# Control_System.net
KiCad netlist of a schematic drawn in Altium Designer
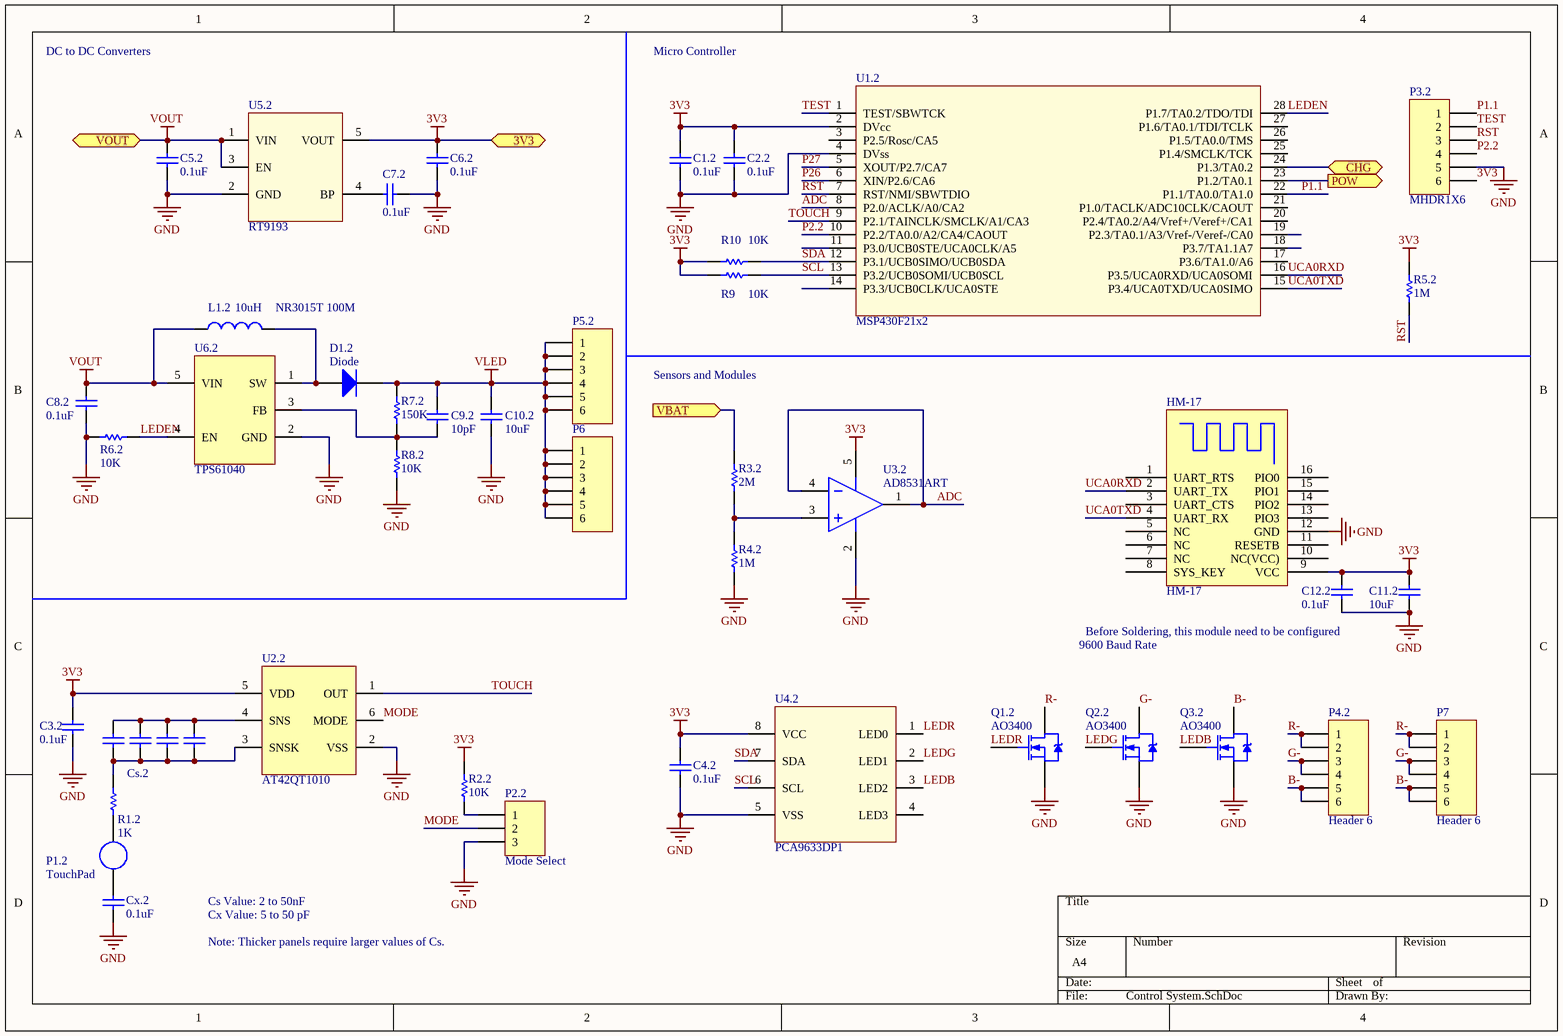
[diagram p0: Control System.SchDoc]

(export (version "E")
  (design (tool "Eeschema 10.0.6"))
  (components
    (comp (ref "C1.2")
      (value "0.1uF")
      (footprint "D0603")
      (description "Capacitor")
      (fields (field (name "Comment") "0603") (field (name "PUBLISHER") "Altium Limited"))
      (libsource (lib "Miscellaneous Devices") (part "Cap"))
    )
    (comp (ref "C2.2")
      (value "0.1uF")
      (footprint "D0603")
      (description "Capacitor")
      (fields (field (name "Comment") "0603") (field (name "PUBLISHER") "Altium Limited"))
      (libsource (lib "Miscellaneous Devices") (part "Cap"))
    )
    (comp (ref "C3.2")
      (value "0.1uF")
      (footprint "D0603")
      (description "Capacitor")
      (fields (field (name "Comment") "0603") (field (name "PUBLISHER") "Altium Limited"))
      (libsource (lib "Miscellaneous Devices") (part "Cap"))
    )
    (comp (ref "C4.2")
      (value "0.1uF")
      (footprint "D0603")
      (description "Capacitor")
      (fields (field (name "Comment") "0603") (field (name "PUBLISHER") "Altium Limited"))
      (libsource (lib "Miscellaneous Devices") (part "Cap"))
    )
    (comp (ref "C5.2")
      (value "0.1uF")
      (footprint "D0603")
      (description "Capacitor")
      (fields (field (name "Comment") "0603") (field (name "PUBLISHER") "Altium Limited"))
      (libsource (lib "Miscellaneous Devices") (part "Cap"))
    )
    (comp (ref "C6.2")
      (value "0.1uF")
      (footprint "D0603")
      (description "Capacitor")
      (fields (field (name "Comment") "0603") (field (name "PUBLISHER") "Altium Limited"))
      (libsource (lib "Miscellaneous Devices") (part "Cap"))
    )
    (comp (ref "C7.2")
      (value "0.1uF")
      (footprint "D0603")
      (description "Capacitor")
      (fields (field (name "Comment") "0603") (field (name "PUBLISHER") "Altium Limited"))
      (libsource (lib "Miscellaneous Devices") (part "Cap"))
    )
    (comp (ref "C8.2")
      (value "0.1uF")
      (footprint "D0603")
      (description "Capacitor")
      (fields (field (name "Comment") "0603") (field (name "PUBLISHER") "Altium Limited"))
      (libsource (lib "Miscellaneous Devices") (part "Cap"))
    )
    (comp (ref "C9.2")
      (value "10pF")
      (footprint "D0603")
      (description "Capacitor")
      (fields (field (name "Comment") "0603") (field (name "PUBLISHER") "Altium Limited"))
      (libsource (lib "Miscellaneous Devices") (part "Cap"))
    )
    (comp (ref "C10.2")
      (value "10uF")
      (footprint "D0805")
      (description "Capacitor")
      (fields (field (name "Comment") "0603") (field (name "PUBLISHER") "Altium Limited"))
      (libsource (lib "Miscellaneous Devices") (part "Cap"))
    )
    (comp (ref "C11.2")
      (value "10uF")
      (footprint "D0603")
      (description "Capacitor")
      (fields (field (name "Comment") "0603") (field (name "PUBLISHER") "Altium Limited"))
      (libsource (lib "Miscellaneous Devices") (part "Cap"))
    )
    (comp (ref "C12.2")
      (value "0.1uF")
      (footprint "D0603")
      (description "Capacitor")
      (fields (field (name "Comment") "0603") (field (name "PUBLISHER") "Altium Limited"))
      (libsource (lib "Miscellaneous Devices") (part "Cap"))
    )
    (comp (ref "Cs.2")
      (value "0603")
      (footprint "D0603")
      (description "Capacitor")
      (fields (field (name "PUBLISHER") "Altium Limited"))
      (libsource (lib "Miscellaneous Devices") (part "Cap"))
    )
    (comp (ref "Cs1")
      (value "0603")
      (footprint "D0603")
      (description "Capacitor")
      (fields (field (name "PUBLISHER") "Altium Limited"))
      (libsource (lib "Miscellaneous Devices") (part "Cap"))
    )
    (comp (ref "Cs2")
      (value "0603")
      (footprint "D0603")
      (description "Capacitor")
      (fields (field (name "PUBLISHER") "Altium Limited"))
      (libsource (lib "Miscellaneous Devices") (part "Cap"))
    )
    (comp (ref "Cs3")
      (value "0603")
      (footprint "D0603")
      (description "Capacitor")
      (fields (field (name "PUBLISHER") "Altium Limited"))
      (libsource (lib "Miscellaneous Devices") (part "Cap"))
    )
    (comp (ref "Cx.2")
      (value "0.1uF")
      (footprint "D0603")
      (description "Capacitor")
      (fields (field (name "Comment") "0603") (field (name "PUBLISHER") "Altium Limited"))
      (libsource (lib "Miscellaneous Devices") (part "Cap"))
    )
    (comp (ref "D1.2")
      (value "Diode")
      (footprint "DO214AC_SMA")
      (description "Default Diode")
      (fields (field (name "PUBLISHER") "Altium Limited"))
      (libsource (lib "Miscellaneous Devices") (part "Diode"))
    )
    (comp (ref "HM-17")
      (value "HM-17")
      (footprint "HM_05_06_07_11_13_17")
      (libsource (lib "Modules") (part "HM-17"))
    )
    (comp (ref "L1.2")
      (value "NR3015T 100M")
      (footprint "Inductor.3030")
      (description "Inductor")
      (fields (field (name "ALTIUM_VALUE") "10uH") (field (name "PUBLISHER") "Altium Limited"))
      (libsource (lib "Miscellaneous Devices") (part "Inductor"))
    )
    (comp (ref "P1.2")
      (value "TouchPad")
      (footprint "HDR1X2 1.27")
      (libsource (lib "Miscellaneous Connectors") (part "TouchPad"))
    )
    (comp (ref "P2.2")
      (value "Mode Select")
      (footprint "HDR1X3 1.27")
      (description "Header, 3-Pin")
      (fields (field (name "PUBLISHER") "Altium Limited"))
      (libsource (lib "Miscellaneous Connectors") (part "Header 3"))
    )
    (comp (ref "P3.2")
      (value "MHDR1X6")
      (footprint "HDR1X6 1.27")
      (description "Header, 6-Pin")
      (fields (field (name "PUBLISHER") "Altium Limited"))
      (libsource (lib "Miscellaneous Connectors") (part "MHDR1X6"))
    )
    (comp (ref "P4.2")
      (value "Header 6")
      (footprint "HDR1X6 1.27")
      (description "Header, 6-Pin")
      (fields (field (name "PUBLISHER") "Altium Limited"))
      (libsource (lib "Miscellaneous Connectors") (part "Header 6"))
    )
    (comp (ref "P5.2")
      (value "Header 6")
      (footprint "HDR1X6 1.27")
      (description "Header, 6-Pin")
      (fields (field (name "PUBLISHER") "Altium Limited"))
      (libsource (lib "Miscellaneous Connectors") (part "Header 6"))
    )
    (comp (ref "P6")
      (value "Header 6")
      (footprint "HDR1X6 1.27")
      (description "Header, 6-Pin")
      (fields (field (name "PUBLISHER") "Altium Limited"))
      (libsource (lib "Miscellaneous Connectors") (part "Header 6"))
    )
    (comp (ref "P7")
      (value "Header 6")
      (footprint "HDR1X6 1.27")
      (description "Header, 6-Pin")
      (fields (field (name "PUBLISHER") "Altium Limited"))
      (libsource (lib "Miscellaneous Connectors") (part "Header 6"))
    )
    (comp (ref "Q1.2")
      (value "AO3400")
      (footprint "SOT23_N")
      (description "N-Channel Power MOSFET")
      (fields (field (name "PUBLISHER") "Altium Limited"))
      (libsource (lib "Miscellaneous Devices") (part "NMOS-2"))
    )
    (comp (ref "Q2.2")
      (value "AO3400")
      (footprint "SOT23_N")
      (description "N-Channel Power MOSFET")
      (fields (field (name "PUBLISHER") "Altium Limited"))
      (libsource (lib "Miscellaneous Devices") (part "NMOS-2"))
    )
    (comp (ref "Q3.2")
      (value "AO3400")
      (footprint "SOT23_N")
      (description "N-Channel Power MOSFET")
      (fields (field (name "PUBLISHER") "Altium Limited"))
      (libsource (lib "Miscellaneous Devices") (part "NMOS-2"))
    )
    (comp (ref "R1.2")
      (value "1K")
      (footprint "D0603")
      (description "Resistor")
      (fields (field (name "Comment") "0603") (field (name "PUBLISHER") "Altium Limited"))
      (libsource (lib "Miscellaneous Devices") (part "Res1"))
    )
    (comp (ref "R2.2")
      (value "10K")
      (footprint "D0603")
      (description "Resistor")
      (fields (field (name "Comment") "0603") (field (name "PUBLISHER") "Altium Limited"))
      (libsource (lib "Miscellaneous Devices") (part "Res1"))
    )
    (comp (ref "R3.2")
      (value "2M")
      (footprint "D0603")
      (description "Resistor")
      (fields (field (name "Comment") "0603") (field (name "PUBLISHER") "Altium Limited"))
      (libsource (lib "Miscellaneous Devices") (part "Res1"))
    )
    (comp (ref "R4.2")
      (value "1M")
      (footprint "D0603")
      (description "Resistor")
      (fields (field (name "Comment") "0603") (field (name "PUBLISHER") "Altium Limited"))
      (libsource (lib "Miscellaneous Devices") (part "Res1"))
    )
    (comp (ref "R5.2")
      (value "1M")
      (footprint "D0603")
      (description "Resistor")
      (fields (field (name "Comment") "0603") (field (name "PUBLISHER") "Altium Limited"))
      (libsource (lib "Miscellaneous Devices") (part "Res1"))
    )
    (comp (ref "R6.2")
      (value "10K")
      (footprint "D0603")
      (description "Resistor")
      (fields (field (name "Comment") "0603") (field (name "PUBLISHER") "Altium Limited"))
      (libsource (lib "Miscellaneous Devices") (part "Res1"))
    )
    (comp (ref "R7.2")
      (value "150K")
      (footprint "D0603")
      (description "Resistor")
      (fields (field (name "Comment") "0603") (field (name "PUBLISHER") "Altium Limited"))
      (libsource (lib "Miscellaneous Devices") (part "Res1"))
    )
    (comp (ref "R8.2")
      (value "10K")
      (footprint "D0603")
      (description "Resistor")
      (fields (field (name "Comment") "0603") (field (name "PUBLISHER") "Altium Limited"))
      (libsource (lib "Miscellaneous Devices") (part "Res1"))
    )
    (comp (ref "R9")
      (value "10K")
      (footprint "D0603")
      (description "Resistor")
      (fields (field (name "Comment") "0603") (field (name "PUBLISHER") "Altium Limited"))
      (libsource (lib "Miscellaneous Devices") (part "Res1"))
    )
    (comp (ref "R10")
      (value "10K")
      (footprint "D0603")
      (description "Resistor")
      (fields (field (name "Comment") "0603") (field (name "PUBLISHER") "Altium Limited"))
      (libsource (lib "Miscellaneous Devices") (part "Res1"))
    )
    (comp (ref "U1.2")
      (value "MSP430F21x2")
      (footprint "TSSOP28")
      (description "MSP430F21x2_PW")
      (libsource (lib "Ti Microcontrollers MSP430") (part "MSP430F21x2_PW"))
    )
    (comp (ref "U2.2")
      (value "AT42QT1010")
      (footprint "SOT23-6")
      (description "AT42QT1010 SOT23-6")
      (libsource (lib "Touch Sense") (part "AT42QT1010"))
    )
    (comp (ref "U3.2")
      (value "AD8531ART")
      (footprint "SOT23-5")
      (description "Low Cost, 250 mA Output Single-Supply Amplifier")
      (fields (field (name "PUBLISHER") "Altium Limited"))
      (libsource (lib "AD Operational Amplifier") (part "AD8531ART"))
    )
    (comp (ref "U4.2")
      (value "PCA9633DP1")
      (footprint "TSSOP8")
      (libsource (lib "LED Drivers & Controllers") (part "PCA9633DP1"))
    )
    (comp (ref "U5.2")
      (value "RT9193")
      (footprint "SC70-5")
      (description "3V3 Voltage Regulator")
      (libsource (lib "DC to DC") (part "RT9193"))
    )
    (comp (ref "U6.2") (value "TPS61040") (footprint "SOT23-5") (libsource (lib "Ti") (part "TPS61040")))
  )
  (nets
    (net (code "1") (name "/ADC") (class "Default")
      (node (ref "U1.2") (pin "8") (pinfunction "P2.0/ACLK/A0/CA2_8") (pintype "passive"))
      (node (ref "U3.2") (pin "1") (pinfunction "OUT_1") (pintype "passive"))
      (node (ref "U3.2") (pin "4") (pinfunction "IN-_4") (pintype "passive"))
    )
    (net (code "2") (name "/B-") (class "Default")
      (node (ref "P4.2") (pin "5") (pinfunction "5_5") (pintype "passive"))
      (node (ref "P4.2") (pin "6") (pinfunction "6_6") (pintype "passive"))
      (node (ref "P7") (pin "5") (pinfunction "5_5") (pintype "passive"))
      (node (ref "P7") (pin "6") (pinfunction "6_6") (pintype "passive"))
      (node (ref "Q3.2") (pin "2") (pinfunction "D_2") (pintype "passive"))
    )
    (net (code "3") (name "/CHG") (class "Default")
      (node (ref "U1.2") (pin "24") (pinfunction "P1.3/TA0.2_24") (pintype "passive"))
    )
    (net (code "4") (name "/G-") (class "Default")
      (node (ref "P4.2") (pin "3") (pinfunction "3_3") (pintype "passive"))
      (node (ref "P4.2") (pin "4") (pinfunction "4_4") (pintype "passive"))
      (node (ref "P7") (pin "3") (pinfunction "3_3") (pintype "passive"))
      (node (ref "P7") (pin "4") (pinfunction "4_4") (pintype "passive"))
      (node (ref "Q2.2") (pin "2") (pinfunction "D_2") (pintype "passive"))
    )
    (net (code "5") (name "/LEDB") (class "Default")
      (node (ref "Q3.2") (pin "1") (pinfunction "G_1") (pintype "passive"))
      (node (ref "U4.2") (pin "3") (pinfunction "LED2_3") (pintype "passive"))
    )
    (net (code "6") (name "/LEDEN") (class "Default")
      (node (ref "R6.2") (pin "1") (pinfunction "1_1") (pintype "passive"))
      (node (ref "U1.2") (pin "28") (pinfunction "P1.7/TA0.2/TDO/TDI_28") (pintype "passive"))
      (node (ref "U6.2") (pin "4") (pinfunction "EN_4") (pintype "passive"))
    )
    (net (code "7") (name "/LEDG") (class "Default")
      (node (ref "Q2.2") (pin "1") (pinfunction "G_1") (pintype "passive"))
      (node (ref "U4.2") (pin "2") (pinfunction "LED1_2") (pintype "passive"))
    )
    (net (code "8") (name "/LEDR") (class "Default")
      (node (ref "Q1.2") (pin "1") (pinfunction "G_1") (pintype "passive"))
      (node (ref "U4.2") (pin "1") (pinfunction "LED0_1") (pintype "passive"))
    )
    (net (code "9") (name "/MODE") (class "Default")
      (node (ref "P2.2") (pin "2") (pinfunction "2_2") (pintype "passive"))
      (node (ref "U2.2") (pin "6") (pinfunction "MODE_6") (pintype "passive"))
    )
    (net (code "10") (name "/P1.1") (class "Default")
      (node (ref "P3.2") (pin "1") (pinfunction "1_1") (pintype "passive"))
      (node (ref "U1.2") (pin "22") (pinfunction "P1.1/TA0.0/TA1.0_22") (pintype "passive"))
    )
    (net (code "11") (name "/P2.2") (class "Default")
      (node (ref "P3.2") (pin "4") (pinfunction "4_4") (pintype "passive"))
      (node (ref "U1.2") (pin "10") (pinfunction "P2.2/TA0.0/A2/CA4/CAOUT_10") (pintype "passive"))
    )
    (net (code "12") (name "/P26") (class "Default")
      (node (ref "U1.2") (pin "6") (pinfunction "XIN/P2.6/CA6_6") (pintype "passive"))
    )
    (net (code "13") (name "/P27") (class "Default")
      (node (ref "U1.2") (pin "5") (pinfunction "XOUT/P2.7/CA7_5") (pintype "passive"))
    )
    (net (code "14") (name "/POW") (class "Default")
      (node (ref "U1.2") (pin "23") (pinfunction "P1.2/TA0.1_23") (pintype "passive"))
    )
    (net (code "15") (name "/R-") (class "Default")
      (node (ref "P4.2") (pin "1") (pinfunction "1_1") (pintype "passive"))
      (node (ref "P4.2") (pin "2") (pinfunction "2_2") (pintype "passive"))
      (node (ref "P7") (pin "1") (pinfunction "1_1") (pintype "passive"))
      (node (ref "P7") (pin "2") (pinfunction "2_2") (pintype "passive"))
      (node (ref "Q1.2") (pin "2") (pinfunction "D_2") (pintype "passive"))
    )
    (net (code "16") (name "/RST") (class "Default")
      (node (ref "P3.2") (pin "3") (pinfunction "3_3") (pintype "passive"))
      (node (ref "R5.2") (pin "1") (pinfunction "1_1") (pintype "passive"))
      (node (ref "U1.2") (pin "7") (pinfunction "RST/NMI/SBWTDIO_7") (pintype "passive"))
    )
    (net (code "17") (name "/SCL") (class "Default")
      (node (ref "R9") (pin "1") (pinfunction "1_1") (pintype "passive"))
      (node (ref "U1.2") (pin "13") (pinfunction "P3.2/UCB0SOMI/UCB0SCL_13") (pintype "passive"))
      (node (ref "U4.2") (pin "6") (pinfunction "SCL_6") (pintype "passive"))
    )
    (net (code "18") (name "/SDA") (class "Default")
      (node (ref "R10") (pin "1") (pinfunction "1_1") (pintype "passive"))
      (node (ref "U1.2") (pin "12") (pinfunction "P3.1/UCB0SIMO/UCB0SDA_12") (pintype "passive"))
      (node (ref "U4.2") (pin "7") (pinfunction "SDA_7") (pintype "passive"))
    )
    (net (code "19") (name "/TEST") (class "Default")
      (node (ref "P3.2") (pin "2") (pinfunction "2_2") (pintype "passive"))
      (node (ref "U1.2") (pin "1") (pinfunction "TEST/SBWTCK_1") (pintype "passive"))
    )
    (net (code "20") (name "/TOUCH") (class "Default")
      (node (ref "U1.2") (pin "9") (pinfunction "P2.1/TAINCLK/SMCLK/A1/CA3_9") (pintype "passive"))
      (node (ref "U2.2") (pin "1") (pinfunction "OUT_1") (pintype "passive"))
    )
    (net (code "21") (name "/UCA0RXD") (class "Default")
      (node (ref "HM-17") (pin "2") (pinfunction "UART_TX_2") (pintype "passive"))
      (node (ref "U1.2") (pin "16") (pinfunction "P3.5/UCA0RXD/UCA0SOMI_16") (pintype "passive"))
    )
    (net (code "22") (name "/UCA0TXD") (class "Default")
      (node (ref "HM-17") (pin "4") (pinfunction "UART_RX_4") (pintype "passive"))
      (node (ref "U1.2") (pin "15") (pinfunction "P3.4/UCA0TXD/UCA0SIMO_15") (pintype "passive"))
    )
    (net (code "23") (name "/VBAT") (class "Default")
      (node (ref "R3.2") (pin "2") (pinfunction "2_2") (pintype "passive"))
    )
    (net (code "24") (name "3V3") (class "Default")
      (node (ref "C1.2") (pin "2") (pinfunction "2_2") (pintype "passive"))
      (node (ref "C11.2") (pin "1") (pinfunction "1_1") (pintype "passive"))
      (node (ref "C12.2") (pin "1") (pinfunction "1_1") (pintype "passive"))
      (node (ref "C2.2") (pin "2") (pinfunction "2_2") (pintype "passive"))
      (node (ref "C3.2") (pin "2") (pinfunction "2_2") (pintype "passive"))
      (node (ref "C4.2") (pin "2") (pinfunction "2_2") (pintype "passive"))
      (node (ref "C6.2") (pin "2") (pinfunction "2_2") (pintype "passive"))
      (node (ref "HM-17") (pin "9") (pinfunction "VCC_9") (pintype "passive"))
      (node (ref "P3.2") (pin "6") (pinfunction "6_6") (pintype "passive"))
      (node (ref "R10") (pin "2") (pinfunction "2_2") (pintype "passive"))
      (node (ref "R2.2") (pin "2") (pinfunction "2_2") (pintype "passive"))
      (node (ref "R5.2") (pin "2") (pinfunction "2_2") (pintype "passive"))
      (node (ref "R9") (pin "2") (pinfunction "2_2") (pintype "passive"))
      (node (ref "U1.2") (pin "2") (pinfunction "DVcc_2") (pintype "passive"))
      (node (ref "U2.2") (pin "5") (pinfunction "VDD_5") (pintype "passive"))
      (node (ref "U3.2") (pin "5") (pinfunction "V+_5") (pintype "passive"))
      (node (ref "U4.2") (pin "8") (pinfunction "VCC_8") (pintype "passive"))
      (node (ref "U5.2") (pin "5") (pinfunction "VOUT_5") (pintype "passive"))
    )
    (net (code "25") (name "GND") (class "Default")
      (node (ref "C1.2") (pin "1") (pinfunction "1_1") (pintype "passive"))
      (node (ref "C10.2") (pin "2") (pinfunction "2_2") (pintype "passive"))
      (node (ref "C11.2") (pin "2") (pinfunction "2_2") (pintype "passive"))
      (node (ref "C12.2") (pin "2") (pinfunction "2_2") (pintype "passive"))
      (node (ref "C2.2") (pin "1") (pinfunction "1_1") (pintype "passive"))
      (node (ref "C3.2") (pin "1") (pinfunction "1_1") (pintype "passive"))
      (node (ref "C4.2") (pin "1") (pinfunction "1_1") (pintype "passive"))
      (node (ref "C5.2") (pin "1") (pinfunction "1_1") (pintype "passive"))
      (node (ref "C6.2") (pin "1") (pinfunction "1_1") (pintype "passive"))
      (node (ref "C7.2") (pin "1") (pinfunction "1_1") (pintype "passive"))
      (node (ref "C8.2") (pin "2") (pinfunction "2_2") (pintype "passive"))
      (node (ref "Cx.2") (pin "1") (pinfunction "1_1") (pintype "passive"))
      (node (ref "HM-17") (pin "12") (pinfunction "GND_12") (pintype "passive"))
      (node (ref "P2.2") (pin "3") (pinfunction "3_3") (pintype "passive"))
      (node (ref "P3.2") (pin "5") (pinfunction "5_5") (pintype "passive"))
      (node (ref "Q1.2") (pin "3") (pinfunction "S_3") (pintype "passive"))
      (node (ref "Q2.2") (pin "3") (pinfunction "S_3") (pintype "passive"))
      (node (ref "Q3.2") (pin "3") (pinfunction "S_3") (pintype "passive"))
      (node (ref "R4.2") (pin "1") (pinfunction "1_1") (pintype "passive"))
      (node (ref "R6.2") (pin "2") (pinfunction "2_2") (pintype "passive"))
      (node (ref "R8.2") (pin "1") (pinfunction "1_1") (pintype "passive"))
      (node (ref "U1.2") (pin "4") (pinfunction "DVss_4") (pintype "passive"))
      (node (ref "U2.2") (pin "2") (pinfunction "VSS_2") (pintype "passive"))
      (node (ref "U3.2") (pin "2") (pinfunction "V-_2") (pintype "power_in"))
      (node (ref "U4.2") (pin "5") (pinfunction "VSS_5") (pintype "passive"))
      (node (ref "U5.2") (pin "2") (pinfunction "GND_2") (pintype "passive"))
      (node (ref "U6.2") (pin "2") (pinfunction "GND_2") (pintype "passive"))
    )
    (net (code "26") (name "Net-(Cx.2-Pad2)") (class "Default")
      (node (ref "Cx.2") (pin "2") (pinfunction "2_2") (pintype "passive"))
      (node (ref "P1.2") (pin "2") (pinfunction "Node_2") (pintype "passive"))
    )
    (net (code "27") (name "Net-(D1.2-A)") (class "Default")
      (node (ref "D1.2") (pin "1") (pinfunction "A_1") (pintype "passive"))
      (node (ref "L1.2") (pin "2") (pinfunction "2_2") (pintype "passive"))
      (node (ref "U6.2") (pin "1") (pinfunction "SW_1") (pintype "passive"))
    )
    (net (code "28") (name "Net-(P1.2-Node-Pad1)") (class "Default")
      (node (ref "P1.2") (pin "1") (pinfunction "Node_1") (pintype "passive"))
      (node (ref "R1.2") (pin "2") (pinfunction "2_2") (pintype "passive"))
    )
    (net (code "29") (name "Net-(P2.2-Pad1)") (class "Default")
      (node (ref "P2.2") (pin "1") (pinfunction "1_1") (pintype "passive"))
      (node (ref "R2.2") (pin "1") (pinfunction "1_1") (pintype "passive"))
    )
    (net (code "30") (name "Net-(U2.2-SNS)") (class "Default")
      (node (ref "Cs.2") (pin "1") (pinfunction "1_1") (pintype "passive"))
      (node (ref "Cs1") (pin "1") (pinfunction "1_1") (pintype "passive"))
      (node (ref "Cs2") (pin "1") (pinfunction "1_1") (pintype "passive"))
      (node (ref "Cs3") (pin "1") (pinfunction "1_1") (pintype "passive"))
      (node (ref "U2.2") (pin "4") (pinfunction "SNS_4") (pintype "passive"))
    )
    (net (code "31") (name "Net-(U2.2-SNSK)") (class "Default")
      (node (ref "Cs.2") (pin "2") (pinfunction "2_2") (pintype "passive"))
      (node (ref "Cs1") (pin "2") (pinfunction "2_2") (pintype "passive"))
      (node (ref "Cs2") (pin "2") (pinfunction "2_2") (pintype "passive"))
      (node (ref "Cs3") (pin "2") (pinfunction "2_2") (pintype "passive"))
      (node (ref "R1.2") (pin "1") (pinfunction "1_1") (pintype "passive"))
      (node (ref "U2.2") (pin "3") (pinfunction "SNSK_3") (pintype "passive"))
    )
    (net (code "32") (name "Net-(U3.2-IN+)") (class "Default")
      (node (ref "R3.2") (pin "1") (pinfunction "1_1") (pintype "passive"))
      (node (ref "R4.2") (pin "2") (pinfunction "2_2") (pintype "passive"))
      (node (ref "U3.2") (pin "3") (pinfunction "IN+_3") (pintype "passive"))
    )
    (net (code "33") (name "Net-(U5.2-BP)") (class "Default")
      (node (ref "C7.2") (pin "2") (pinfunction "2_2") (pintype "passive"))
      (node (ref "U5.2") (pin "4") (pinfunction "BP_4") (pintype "passive"))
    )
    (net (code "34") (name "Net-(U6.2-FB)") (class "Default")
      (node (ref "C9.2") (pin "2") (pinfunction "2_2") (pintype "passive"))
      (node (ref "R7.2") (pin "2") (pinfunction "2_2") (pintype "passive"))
      (node (ref "R8.2") (pin "2") (pinfunction "2_2") (pintype "passive"))
      (node (ref "U6.2") (pin "3") (pinfunction "FB_3") (pintype "passive"))
    )
    (net (code "35") (name "VLED") (class "Default")
      (node (ref "C10.2") (pin "1") (pinfunction "1_1") (pintype "passive"))
      (node (ref "C9.2") (pin "1") (pinfunction "1_1") (pintype "passive"))
      (node (ref "D1.2") (pin "2") (pinfunction "K_2") (pintype "passive"))
      (node (ref "P5.2") (pin "1") (pinfunction "1_1") (pintype "passive"))
      (node (ref "P5.2") (pin "2") (pinfunction "2_2") (pintype "passive"))
      (node (ref "P5.2") (pin "3") (pinfunction "3_3") (pintype "passive"))
      (node (ref "P5.2") (pin "4") (pinfunction "4_4") (pintype "passive"))
      (node (ref "P5.2") (pin "5") (pinfunction "5_5") (pintype "passive"))
      (node (ref "P5.2") (pin "6") (pinfunction "6_6") (pintype "passive"))
      (node (ref "P6") (pin "1") (pinfunction "1_1") (pintype "passive"))
      (node (ref "P6") (pin "2") (pinfunction "2_2") (pintype "passive"))
      (node (ref "P6") (pin "3") (pinfunction "3_3") (pintype "passive"))
      (node (ref "P6") (pin "4") (pinfunction "4_4") (pintype "passive"))
      (node (ref "P6") (pin "5") (pinfunction "5_5") (pintype "passive"))
      (node (ref "P6") (pin "6") (pinfunction "6_6") (pintype "passive"))
      (node (ref "R7.2") (pin "1") (pinfunction "1_1") (pintype "passive"))
    )
    (net (code "36") (name "VOUT") (class "Default")
      (node (ref "C5.2") (pin "2") (pinfunction "2_2") (pintype "passive"))
      (node (ref "C8.2") (pin "1") (pinfunction "1_1") (pintype "passive"))
      (node (ref "L1.2") (pin "1") (pinfunction "1_1") (pintype "passive"))
      (node (ref "U5.2") (pin "1") (pinfunction "VIN_1") (pintype "passive"))
      (node (ref "U5.2") (pin "3") (pinfunction "EN_3") (pintype "passive"))
      (node (ref "U6.2") (pin "5") (pinfunction "VIN_5") (pintype "passive"))
    )
    (net (code "37") (name "unconnected-(HM-17-NC(VCC)-Pad10)") (class "Default")
      (node (ref "HM-17") (pin "10") (pinfunction "NC(VCC)_10") (pintype "passive"))
    )
    (net (code "38") (name "unconnected-(HM-17-NC-Pad5)") (class "Default")
      (node (ref "HM-17") (pin "5") (pinfunction "NC_5") (pintype "passive"))
    )
    (net (code "39") (name "unconnected-(HM-17-NC-Pad6)") (class "Default")
      (node (ref "HM-17") (pin "6") (pinfunction "NC_6") (pintype "passive"))
    )
    (net (code "40") (name "unconnected-(HM-17-NC-Pad7)") (class "Default")
      (node (ref "HM-17") (pin "7") (pinfunction "NC_7") (pintype "passive"))
    )
    (net (code "41") (name "unconnected-(HM-17-PIO0-Pad16)") (class "Default")
      (node (ref "HM-17") (pin "16") (pinfunction "PIO0_16") (pintype "passive"))
    )
    (net (code "42") (name "unconnected-(HM-17-PIO1-Pad15)") (class "Default")
      (node (ref "HM-17") (pin "15") (pinfunction "PIO1_15") (pintype "passive"))
    )
    (net (code "43") (name "unconnected-(HM-17-PIO2-Pad14)") (class "Default")
      (node (ref "HM-17") (pin "14") (pinfunction "PIO2_14") (pintype "passive"))
    )
    (net (code "44") (name "unconnected-(HM-17-PIO3-Pad13)") (class "Default")
      (node (ref "HM-17") (pin "13") (pinfunction "PIO3_13") (pintype "passive"))
    )
    (net (code "45") (name "unconnected-(HM-17-RESETB-Pad11)") (class "Default")
      (node (ref "HM-17") (pin "11") (pinfunction "RESETB_11") (pintype "passive"))
    )
    (net (code "46") (name "unconnected-(HM-17-SYS_KEY-Pad8)") (class "Default")
      (node (ref "HM-17") (pin "8") (pinfunction "SYS_KEY_8") (pintype "passive"))
    )
    (net (code "47") (name "unconnected-(HM-17-UART_CTS-Pad3)") (class "Default")
      (node (ref "HM-17") (pin "3") (pinfunction "UART_CTS_3") (pintype "passive"))
    )
    (net (code "48") (name "unconnected-(HM-17-UART_RTS-Pad1)") (class "Default")
      (node (ref "HM-17") (pin "1") (pinfunction "UART_RTS_1") (pintype "passive"))
    )
    (net (code "49") (name "unconnected-(U1.2-P1.0{slash}TACLK{slash}ADC10CLK{slash}CAOUT-Pad21)") (class "Default")
      (node (ref "U1.2") (pin "21") (pinfunction "P1.0/TACLK/ADC10CLK/CAOUT_21") (pintype "passive"))
    )
    (net (code "50") (name "unconnected-(U1.2-P1.4{slash}SMCLK{slash}TCK-Pad25)") (class "Default")
      (node (ref "U1.2") (pin "25") (pinfunction "P1.4/SMCLK/TCK_25") (pintype "passive"))
    )
    (net (code "51") (name "unconnected-(U1.2-P1.5{slash}TA0.0{slash}TMS-Pad26)") (class "Default")
      (node (ref "U1.2") (pin "26") (pinfunction "P1.5/TA0.0/TMS_26") (pintype "passive"))
    )
    (net (code "52") (name "unconnected-(U1.2-P1.6{slash}TA0.1{slash}TDI{slash}TCLK-Pad27)") (class "Default")
      (node (ref "U1.2") (pin "27") (pinfunction "P1.6/TA0.1/TDI/TCLK_27") (pintype "passive"))
    )
    (net (code "53") (name "unconnected-(U1.2-P2.3{slash}TA0.1{slash}A3{slash}Vref-{slash}Veref-{slash}CA0-Pad19)") (class "Default")
      (node (ref "U1.2") (pin "19") (pinfunction "P2.3/TA0.1/A3/Vref-/Veref-/CA0_19") (pintype "passive"))
    )
    (net (code "54") (name "unconnected-(U1.2-P2.4{slash}TA0.2{slash}A4{slash}Vref+{slash}Veref+{slash}CA1-Pad20)") (class "Default")
      (node (ref "U1.2") (pin "20") (pinfunction "P2.4/TA0.2/A4/Vref+/Veref+/CA1_20") (pintype "passive"))
    )
    (net (code "55") (name "unconnected-(U1.2-P2.5{slash}Rosc{slash}CA5-Pad3)") (class "Default")
      (node (ref "U1.2") (pin "3") (pinfunction "P2.5/Rosc/CA5_3") (pintype "passive"))
    )
    (net (code "56") (name "unconnected-(U1.2-P3.0{slash}UCB0STE{slash}UCA0CLK{slash}A5-Pad11)") (class "Default")
      (node (ref "U1.2") (pin "11") (pinfunction "P3.0/UCB0STE/UCA0CLK/A5_11") (pintype "passive"))
    )
    (net (code "57") (name "unconnected-(U1.2-P3.3{slash}UCB0CLK{slash}UCA0STE-Pad14)") (class "Default")
      (node (ref "U1.2") (pin "14") (pinfunction "P3.3/UCB0CLK/UCA0STE_14") (pintype "passive"))
    )
    (net (code "58") (name "unconnected-(U1.2-P3.6{slash}TA1.0{slash}A6-Pad17)") (class "Default")
      (node (ref "U1.2") (pin "17") (pinfunction "P3.6/TA1.0/A6_17") (pintype "passive"))
    )
    (net (code "59") (name "unconnected-(U1.2-P3.7{slash}TA1.1A7-Pad18)") (class "Default")
      (node (ref "U1.2") (pin "18") (pinfunction "P3.7/TA1.1A7_18") (pintype "passive"))
    )
    (net (code "60") (name "unconnected-(U4.2-LED3-Pad4)") (class "Default")
      (node (ref "U4.2") (pin "4") (pinfunction "LED3_4") (pintype "passive"))
    )
  )
)
